# MCU.net
KiCad netlist of a schematic drawn in Altium Designer
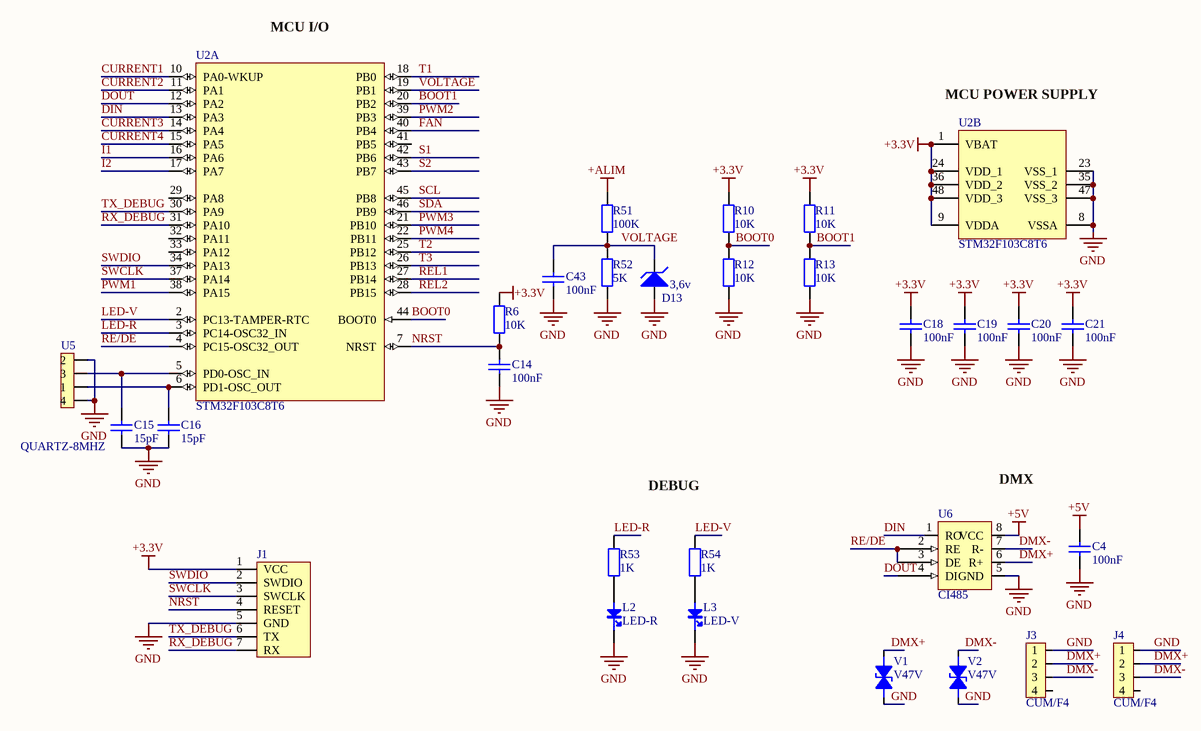
[diagram p0: MCU.SchDoc]

(export (version "E")
  (design (tool "Eeschema 10.0.6"))
  (components
    (comp (ref "C4")
      (value "100nF")
      (footprint "C0603")
      (description "Capacitor")
      (libsource (lib "MyLibrary") (part "Cap"))
    )
    (comp (ref "C14")
      (value "100nF")
      (footprint "C0603")
      (description "Capacitor")
      (libsource (lib "MyLibrary") (part "Cap"))
    )
    (comp (ref "C15")
      (value "15pF")
      (footprint "C0603")
      (description "Capacitor")
      (libsource (lib "MyLibrary") (part "Cap"))
    )
    (comp (ref "C16")
      (value "15pF")
      (footprint "C0603")
      (description "Capacitor")
      (libsource (lib "MyLibrary") (part "Cap"))
    )
    (comp (ref "C18")
      (value "100nF")
      (footprint "C0603")
      (description "Capacitor")
      (libsource (lib "MyLibrary") (part "Cap"))
    )
    (comp (ref "C19")
      (value "100nF")
      (footprint "C0603")
      (description "Capacitor")
      (libsource (lib "MyLibrary") (part "Cap"))
    )
    (comp (ref "C20")
      (value "100nF")
      (footprint "C0603")
      (description "Capacitor")
      (libsource (lib "MyLibrary") (part "Cap"))
    )
    (comp (ref "C21")
      (value "100nF")
      (footprint "C0603")
      (description "Capacitor")
      (libsource (lib "MyLibrary") (part "Cap"))
    )
    (comp (ref "C43")
      (value "100nF")
      (footprint "C0603")
      (description "Capacitor")
      (libsource (lib "MyLibrary") (part "Cap"))
    )
    (comp (ref "D13")
      (value "3,6v")
      (footprint "SOD123")
      (description "Zener Diode")
      (libsource (lib "MyLibrary") (part "D Zener"))
    )
    (comp (ref "J1")
      (value "~")
      (footprint "CON_PROG")
      (description "Programming Connector")
      (libsource (lib "MyLibrary") (part "CON-PROG"))
    )
    (comp (ref "J3")
      (value "CUM/F4")
      (footprint "CNT4S")
      (description "connecteur  4 points")
      (libsource (lib "PROTEL") (part "CUM/F4"))
    )
    (comp (ref "J4")
      (value "CUM/F4")
      (footprint "CNT4S")
      (description "connecteur  4 points")
      (libsource (lib "PROTEL") (part "CUM/F4"))
    )
    (comp (ref "L2")
      (value "LED-R")
      (footprint "LED-R1A")
      (description "LED  piquer ou CMS ou reverse rouge")
      (libsource (lib "PROTEL") (part "LED-R"))
    )
    (comp (ref "L3")
      (value "LED-V")
      (footprint "LED-V1A")
      (description "LED  piquer  ou  CMS verte")
      (libsource (lib "PROTEL") (part "LED-V"))
    )
    (comp (ref "R6")
      (value "10K")
      (footprint "R0603")
      (description "Thin Metal Film Resistor")
      (libsource (lib "MyLibrary") (part "Res"))
    )
    (comp (ref "R10")
      (value "10K")
      (footprint "R0603")
      (description "Thin Metal Film Resistor")
      (libsource (lib "MyLibrary") (part "Res"))
    )
    (comp (ref "R11")
      (value "10K")
      (footprint "R0603")
      (description "Thin Metal Film Resistor")
      (libsource (lib "MyLibrary") (part "Res"))
    )
    (comp (ref "R12")
      (value "10K")
      (footprint "R0603")
      (description "Thin Metal Film Resistor")
      (libsource (lib "MyLibrary") (part "Res"))
    )
    (comp (ref "R13")
      (value "10K")
      (footprint "R0603")
      (description "Thin Metal Film Resistor")
      (libsource (lib "MyLibrary") (part "Res"))
    )
    (comp (ref "R51")
      (value "100K")
      (footprint "R0603")
      (description "Thin Metal Film Resistor")
      (libsource (lib "MyLibrary") (part "Res"))
    )
    (comp (ref "R52")
      (value "5K")
      (footprint "R0603")
      (description "Thin Metal Film Resistor")
      (libsource (lib "MyLibrary") (part "Res"))
    )
    (comp (ref "R53")
      (value "1K")
      (footprint "R0603")
      (description "Thin Metal Film Resistor")
      (libsource (lib "MyLibrary") (part "Res"))
    )
    (comp (ref "R54")
      (value "1K")
      (footprint "R0603")
      (description "Thin Metal Film Resistor")
      (libsource (lib "MyLibrary") (part "Res"))
    )
    (comp (ref "U2")
      (value "STM32F103C8T6")
      (footprint "TQFP-48")
      (libsource (lib "MyLibrary") (part "STM32F103C8T6"))
    )
    (comp (ref "U5")
      (value "QUARTZ-8MHZ")
      (footprint "QUA8G")
      (description "QUARTZ 8 MHZ CMS")
      (libsource (lib "PROTEL") (part "QUARTZ-8MHZ"))
    )
    (comp (ref "U6")
      (value "CI485")
      (footprint "CIA485A")
      (description "DRIVER  RS485")
      (libsource (lib "PROTEL") (part "CI485"))
    )
    (comp (ref "V1")
      (value "V47V")
      (footprint "VAR47A")
      (description "VARISTANCE 47V BOITIER 1206")
      (libsource (lib "PROTEL") (part "V47V"))
    )
    (comp (ref "V2")
      (value "V47V")
      (footprint "VAR47A")
      (description "VARISTANCE 47V BOITIER 1206")
      (libsource (lib "PROTEL") (part "V47V"))
    )
  )
  (nets
    (net (code "1") (name "+3.3V") (class "Default")
      (node (ref "C18") (pin "2") (pinfunction "2_2") (pintype "passive"))
      (node (ref "C19") (pin "2") (pinfunction "2_2") (pintype "passive"))
      (node (ref "C20") (pin "2") (pinfunction "2_2") (pintype "passive"))
      (node (ref "C21") (pin "2") (pinfunction "2_2") (pintype "passive"))
      (node (ref "J1") (pin "1") (pinfunction "VCC_1") (pintype "passive"))
      (node (ref "R10") (pin "2") (pinfunction "2_2") (pintype "passive"))
      (node (ref "R11") (pin "2") (pinfunction "2_2") (pintype "passive"))
      (node (ref "R6") (pin "2") (pinfunction "2_2") (pintype "passive"))
      (node (ref "U2") (pin "1") (pinfunction "VBAT_1") (pintype "power_in"))
      (node (ref "U2") (pin "24") (pinfunction "VDD_1_24") (pintype "power_in"))
      (node (ref "U2") (pin "36") (pinfunction "VDD_2_36") (pintype "power_in"))
      (node (ref "U2") (pin "48") (pinfunction "VDD_3_48") (pintype "power_in"))
      (node (ref "U2") (pin "9") (pinfunction "VDDA_9") (pintype "power_in"))
    )
    (net (code "2") (name "+5V") (class "Default")
      (node (ref "C4") (pin "2") (pinfunction "2_2") (pintype "passive"))
      (node (ref "U6") (pin "8") (pinfunction "VCC_8") (pintype "power_in"))
    )
    (net (code "3") (name "+ALIM") (class "Default")
      (node (ref "R51") (pin "2") (pinfunction "2_2") (pintype "passive"))
    )
    (net (code "4") (name "/BOOT0") (class "Default")
      (node (ref "R10") (pin "1") (pinfunction "1_1") (pintype "passive"))
      (node (ref "R12") (pin "2") (pinfunction "2_2") (pintype "passive"))
      (node (ref "U2") (pin "44") (pinfunction "BOOT0_44") (pintype "input"))
    )
    (net (code "5") (name "/BOOT1") (class "Default")
      (node (ref "R11") (pin "1") (pinfunction "1_1") (pintype "passive"))
      (node (ref "R13") (pin "2") (pinfunction "2_2") (pintype "passive"))
      (node (ref "U2") (pin "20") (pinfunction "PB2_20") (pintype "bidirectional"))
    )
    (net (code "6") (name "/CURRENT1") (class "Default")
      (node (ref "U2") (pin "10") (pinfunction "PA0-WKUP_10") (pintype "bidirectional"))
    )
    (net (code "7") (name "/CURRENT2") (class "Default")
      (node (ref "U2") (pin "11") (pinfunction "PA1_11") (pintype "bidirectional"))
    )
    (net (code "8") (name "/CURRENT3") (class "Default")
      (node (ref "U2") (pin "14") (pinfunction "PA4_14") (pintype "bidirectional"))
    )
    (net (code "9") (name "/CURRENT4") (class "Default")
      (node (ref "U2") (pin "15") (pinfunction "PA5_15") (pintype "bidirectional"))
    )
    (net (code "10") (name "/DIN") (class "Default")
      (node (ref "U2") (pin "13") (pinfunction "PA3_13") (pintype "bidirectional"))
      (node (ref "U6") (pin "1") (pinfunction "RO_1") (pintype "bidirectional"))
    )
    (net (code "11") (name "/DMX+") (class "Default")
      (node (ref "J3") (pin "2") (pinfunction "2_2") (pintype "passive"))
      (node (ref "J4") (pin "2") (pinfunction "2_2") (pintype "passive"))
      (node (ref "U6") (pin "6") (pinfunction "R+_6") (pintype "bidirectional"))
      (node (ref "V1") (pin "1") (pinfunction "1_1") (pintype "passive"))
    )
    (net (code "12") (name "/DMX-") (class "Default")
      (node (ref "J3") (pin "3") (pinfunction "3_3") (pintype "passive"))
      (node (ref "J4") (pin "3") (pinfunction "3_3") (pintype "passive"))
      (node (ref "U6") (pin "7") (pinfunction "R-_7") (pintype "bidirectional"))
      (node (ref "V2") (pin "1") (pinfunction "1_1") (pintype "passive"))
    )
    (net (code "13") (name "/DOUT") (class "Default")
      (node (ref "U2") (pin "12") (pinfunction "PA2_12") (pintype "bidirectional"))
      (node (ref "U6") (pin "4") (pinfunction "DI_4") (pintype "input"))
    )
    (net (code "14") (name "/FAN") (class "Default")
      (node (ref "U2") (pin "40") (pinfunction "PB4_40") (pintype "bidirectional"))
    )
    (net (code "15") (name "/I1") (class "Default")
      (node (ref "U2") (pin "16") (pinfunction "PA6_16") (pintype "bidirectional"))
    )
    (net (code "16") (name "/I2") (class "Default")
      (node (ref "U2") (pin "17") (pinfunction "PA7_17") (pintype "bidirectional"))
    )
    (net (code "17") (name "/LED-R") (class "Default")
      (node (ref "R53") (pin "2") (pinfunction "2_2") (pintype "passive"))
      (node (ref "U2") (pin "3") (pinfunction "PC14-OSC32_IN_3") (pintype "bidirectional"))
    )
    (net (code "18") (name "/LED-V") (class "Default")
      (node (ref "R54") (pin "2") (pinfunction "2_2") (pintype "passive"))
      (node (ref "U2") (pin "2") (pinfunction "PC13-TAMPER-RTC_2") (pintype "bidirectional"))
    )
    (net (code "19") (name "/NRST") (class "Default")
      (node (ref "C14") (pin "2") (pinfunction "2_2") (pintype "passive"))
      (node (ref "J1") (pin "4") (pinfunction "RESET_4") (pintype "passive"))
      (node (ref "R6") (pin "1") (pinfunction "1_1") (pintype "passive"))
      (node (ref "U2") (pin "7") (pinfunction "NRST_7") (pintype "bidirectional"))
    )
    (net (code "20") (name "/PWM1") (class "Default")
      (node (ref "U2") (pin "38") (pinfunction "PA15_38") (pintype "bidirectional"))
    )
    (net (code "21") (name "/PWM2") (class "Default")
      (node (ref "U2") (pin "39") (pinfunction "PB3_39") (pintype "bidirectional"))
    )
    (net (code "22") (name "/PWM3") (class "Default")
      (node (ref "U2") (pin "21") (pinfunction "PB10_21") (pintype "bidirectional"))
    )
    (net (code "23") (name "/PWM4") (class "Default")
      (node (ref "U2") (pin "22") (pinfunction "PB11_22") (pintype "bidirectional"))
    )
    (net (code "24") (name "/REL1") (class "Default")
      (node (ref "U2") (pin "27") (pinfunction "PB14_27") (pintype "bidirectional"))
    )
    (net (code "25") (name "/REL2") (class "Default")
      (node (ref "U2") (pin "28") (pinfunction "PB15_28") (pintype "bidirectional"))
    )
    (net (code "26") (name "/RE{slash}DE") (class "Default")
      (node (ref "U2") (pin "4") (pinfunction "PC15-OSC32_OUT_4") (pintype "bidirectional"))
      (node (ref "U6") (pin "2") (pinfunction "RE_2") (pintype "input"))
      (node (ref "U6") (pin "3") (pinfunction "DE_3") (pintype "input"))
    )
    (net (code "27") (name "/RX_DEBUG") (class "Default")
      (node (ref "J1") (pin "7") (pinfunction "RX_7") (pintype "passive"))
      (node (ref "U2") (pin "31") (pinfunction "PA10_31") (pintype "bidirectional"))
    )
    (net (code "28") (name "/S1") (class "Default")
      (node (ref "U2") (pin "42") (pinfunction "PB6_42") (pintype "bidirectional"))
    )
    (net (code "29") (name "/S2") (class "Default")
      (node (ref "U2") (pin "43") (pinfunction "PB7_43") (pintype "bidirectional"))
    )
    (net (code "30") (name "/SCL") (class "Default")
      (node (ref "U2") (pin "45") (pinfunction "PB8_45") (pintype "bidirectional"))
    )
    (net (code "31") (name "/SDA") (class "Default")
      (node (ref "U2") (pin "46") (pinfunction "PB9_46") (pintype "bidirectional"))
    )
    (net (code "32") (name "/SWCLK") (class "Default")
      (node (ref "J1") (pin "3") (pinfunction "SWCLK_3") (pintype "passive"))
      (node (ref "U2") (pin "37") (pinfunction "PA14_37") (pintype "bidirectional"))
    )
    (net (code "33") (name "/SWDIO") (class "Default")
      (node (ref "J1") (pin "2") (pinfunction "SWDIO_2") (pintype "passive"))
      (node (ref "U2") (pin "34") (pinfunction "PA13_34") (pintype "bidirectional"))
    )
    (net (code "34") (name "/T1") (class "Default")
      (node (ref "U2") (pin "18") (pinfunction "PB0_18") (pintype "bidirectional"))
    )
    (net (code "35") (name "/T2") (class "Default")
      (node (ref "U2") (pin "25") (pinfunction "PB12_25") (pintype "bidirectional"))
    )
    (net (code "36") (name "/T3") (class "Default")
      (node (ref "U2") (pin "26") (pinfunction "PB13_26") (pintype "bidirectional"))
    )
    (net (code "37") (name "/TX_DEBUG") (class "Default")
      (node (ref "J1") (pin "6") (pinfunction "TX_6") (pintype "passive"))
      (node (ref "U2") (pin "30") (pinfunction "PA9_30") (pintype "bidirectional"))
    )
    (net (code "38") (name "/VOLTAGE") (class "Default")
      (node (ref "C43") (pin "2") (pinfunction "2_2") (pintype "passive"))
      (node (ref "D13") (pin "2") (pinfunction "K_2") (pintype "passive"))
      (node (ref "R51") (pin "1") (pinfunction "1_1") (pintype "passive"))
      (node (ref "R52") (pin "2") (pinfunction "2_2") (pintype "passive"))
      (node (ref "U2") (pin "19") (pinfunction "PB1_19") (pintype "bidirectional"))
    )
    (net (code "39") (name "GND") (class "Default")
      (node (ref "C14") (pin "1") (pinfunction "1_1") (pintype "passive"))
      (node (ref "C15") (pin "2") (pinfunction "2_2") (pintype "passive"))
      (node (ref "C16") (pin "1") (pinfunction "1_1") (pintype "passive"))
      (node (ref "C18") (pin "1") (pinfunction "1_1") (pintype "passive"))
      (node (ref "C19") (pin "1") (pinfunction "1_1") (pintype "passive"))
      (node (ref "C20") (pin "1") (pinfunction "1_1") (pintype "passive"))
      (node (ref "C21") (pin "1") (pinfunction "1_1") (pintype "passive"))
      (node (ref "C4") (pin "1") (pinfunction "1_1") (pintype "passive"))
      (node (ref "C43") (pin "1") (pinfunction "1_1") (pintype "passive"))
      (node (ref "D13") (pin "1") (pinfunction "A_1") (pintype "passive"))
      (node (ref "J1") (pin "5") (pinfunction "GND_5") (pintype "passive"))
      (node (ref "J3") (pin "1") (pinfunction "1_1") (pintype "passive"))
      (node (ref "J4") (pin "1") (pinfunction "1_1") (pintype "passive"))
      (node (ref "L2") (pin "2") (pintype "passive"))
      (node (ref "L3") (pin "2") (pintype "passive"))
      (node (ref "R12") (pin "1") (pinfunction "1_1") (pintype "passive"))
      (node (ref "R13") (pin "1") (pinfunction "1_1") (pintype "passive"))
      (node (ref "R52") (pin "1") (pinfunction "1_1") (pintype "passive"))
      (node (ref "U2") (pin "23") (pinfunction "VSS_1_23") (pintype "power_in"))
      (node (ref "U2") (pin "35") (pinfunction "VSS_2_35") (pintype "power_in"))
      (node (ref "U2") (pin "47") (pinfunction "VSS_3_47") (pintype "power_in"))
      (node (ref "U2") (pin "8") (pinfunction "VSSA_8") (pintype "power_in"))
      (node (ref "U5") (pin "2") (pinfunction "2_2") (pintype "passive"))
      (node (ref "U5") (pin "4") (pinfunction "4_4") (pintype "passive"))
      (node (ref "U6") (pin "5") (pinfunction "GND_5") (pintype "power_in"))
      (node (ref "V1") (pin "2") (pinfunction "2_2") (pintype "passive"))
      (node (ref "V2") (pin "2") (pinfunction "2_2") (pintype "passive"))
    )
    (net (code "40") (name "Net-(L2-Pad1)") (class "Default")
      (node (ref "L2") (pin "1") (pintype "passive"))
      (node (ref "R53") (pin "1") (pinfunction "1_1") (pintype "passive"))
    )
    (net (code "41") (name "Net-(L3-Pad1)") (class "Default")
      (node (ref "L3") (pin "1") (pintype "passive"))
      (node (ref "R54") (pin "1") (pinfunction "1_1") (pintype "passive"))
    )
    (net (code "42") (name "Net-(U2A-PD0-OSC_IN)") (class "Default")
      (node (ref "C15") (pin "1") (pinfunction "1_1") (pintype "passive"))
      (node (ref "U2") (pin "5") (pinfunction "PD0-OSC_IN_5") (pintype "bidirectional"))
      (node (ref "U5") (pin "3") (pinfunction "3_3") (pintype "passive"))
    )
    (net (code "43") (name "Net-(U2A-PD1-OSC_OUT)") (class "Default")
      (node (ref "C16") (pin "2") (pinfunction "2_2") (pintype "passive"))
      (node (ref "U2") (pin "6") (pinfunction "PD1-OSC_OUT_6") (pintype "bidirectional"))
      (node (ref "U5") (pin "1") (pinfunction "1_1") (pintype "passive"))
    )
    (net (code "44") (name "unconnected-(J3-Pad4)") (class "Default")
      (node (ref "J3") (pin "4") (pinfunction "4_4") (pintype "passive"))
    )
    (net (code "45") (name "unconnected-(J4-Pad4)") (class "Default")
      (node (ref "J4") (pin "4") (pinfunction "4_4") (pintype "passive"))
    )
    (net (code "46") (name "unconnected-(U2A-PA8-Pad29)") (class "Default")
      (node (ref "U2") (pin "29") (pinfunction "PA8_29") (pintype "bidirectional"))
    )
    (net (code "47") (name "unconnected-(U2A-PA11-Pad32)") (class "Default")
      (node (ref "U2") (pin "32") (pinfunction "PA11_32") (pintype "bidirectional"))
    )
    (net (code "48") (name "unconnected-(U2A-PA12-Pad33)") (class "Default")
      (node (ref "U2") (pin "33") (pinfunction "PA12_33") (pintype "bidirectional"))
    )
    (net (code "49") (name "unconnected-(U2A-PB5-Pad41)") (class "Default")
      (node (ref "U2") (pin "41") (pinfunction "PB5_41") (pintype "bidirectional"))
    )
  )
)
